# btn.net
KiCad netlist of a schematic drawn in Altium Designer
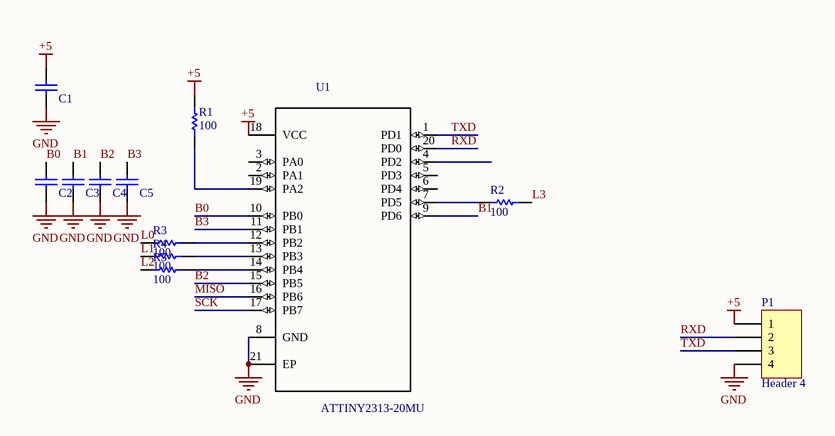
[diagram p0: btn.SchDoc]

(export (version "E")
  (design (tool "Eeschema 10.0.6"))
  (components
    (comp (ref "C1")
      (value "Cap")
      (footprint "0603x")
      (description "Capacitor")
      (fields (field (name "PUBLISHER") "Altium Limited"))
      (libsource (lib "Miscellaneous Devices") (part "Cap"))
    )
    (comp (ref "C2")
      (value "Cap")
      (footprint "0603x")
      (description "Capacitor")
      (fields (field (name "PUBLISHER") "Altium Limited"))
      (libsource (lib "Miscellaneous Devices") (part "Cap"))
    )
    (comp (ref "C3")
      (value "Cap")
      (footprint "0603x")
      (description "Capacitor")
      (fields (field (name "PUBLISHER") "Altium Limited"))
      (libsource (lib "Miscellaneous Devices") (part "Cap"))
    )
    (comp (ref "C4")
      (value "Cap")
      (footprint "0603x")
      (description "Capacitor")
      (fields (field (name "PUBLISHER") "Altium Limited"))
      (libsource (lib "Miscellaneous Devices") (part "Cap"))
    )
    (comp (ref "C5")
      (value "Cap")
      (footprint "0603x")
      (description "Capacitor")
      (fields (field (name "PUBLISHER") "Altium Limited"))
      (libsource (lib "Miscellaneous Devices") (part "Cap"))
    )
    (comp (ref "P1")
      (value "Header 4")
      (footprint "HDR1X4")
      (description "Header, 4-Pin")
      (fields (field (name "PUBLISHER") "Altium Limited"))
      (libsource (lib "Miscellaneous Connectors") (part "Header 4"))
    )
    (comp (ref "R1")
      (value "100")
      (footprint "0402x")
      (description "Resistor")
      (fields (field (name "PUBLISHER") "Altium Limited"))
      (libsource (lib "Miscellaneous Devices") (part "Res1"))
    )
    (comp (ref "R2")
      (value "100")
      (footprint "0603x")
      (description "Resistor")
      (fields (field (name "PUBLISHER") "Altium Limited"))
      (libsource (lib "Miscellaneous Devices") (part "Res1"))
    )
    (comp (ref "R3")
      (value "100")
      (footprint "0603x")
      (description "Resistor")
      (fields (field (name "PUBLISHER") "Altium Limited"))
      (libsource (lib "Miscellaneous Devices") (part "Res1"))
    )
    (comp (ref "R4")
      (value "100")
      (footprint "0603x")
      (description "Resistor")
      (fields (field (name "PUBLISHER") "Altium Limited"))
      (libsource (lib "Miscellaneous Devices") (part "Res1"))
    )
    (comp (ref "R5")
      (value "100")
      (footprint "0603x")
      (description "Resistor")
      (fields (field (name "PUBLISHER") "Altium Limited"))
      (libsource (lib "Miscellaneous Devices") (part "Res1"))
    )
    (comp (ref "U1")
      (value "ATTINY2313-20MU")
      (footprint "*QFN50P400X400X80-21N")
      (description "ATtiny Series 20 MHz 2 KB Flash 128 B SRAM 8-Bit Microcontroller - QFN-20")
      (fields (field (name "MF") "Microchip"))
      (libsource (lib "EDDLib") (part "ATTINY2313-20MU"))
    )
  )
  (nets
    (net (code "1") (name "+5") (class "Default")
      (node (ref "C1") (pin "1") (pinfunction "1_1") (pintype "passive"))
      (node (ref "P1") (pin "1") (pinfunction "1_1") (pintype "passive"))
      (node (ref "R1") (pin "1") (pinfunction "1_1") (pintype "passive"))
      (node (ref "U1") (pin "18") (pinfunction "VCC_18") (pintype "power_in"))
    )
    (net (code "2") (name "/B0") (class "Default")
      (node (ref "C2") (pin "1") (pinfunction "1_1") (pintype "passive"))
      (node (ref "U1") (pin "10") (pinfunction "PB0_10") (pintype "bidirectional"))
    )
    (net (code "3") (name "/B1") (class "Default")
      (node (ref "C3") (pin "1") (pinfunction "1_1") (pintype "passive"))
      (node (ref "U1") (pin "9") (pinfunction "PD6_9") (pintype "bidirectional"))
    )
    (net (code "4") (name "/B2") (class "Default")
      (node (ref "C4") (pin "1") (pinfunction "1_1") (pintype "passive"))
      (node (ref "U1") (pin "15") (pinfunction "PB5_15") (pintype "bidirectional"))
    )
    (net (code "5") (name "/B3") (class "Default")
      (node (ref "C5") (pin "1") (pinfunction "1_1") (pintype "passive"))
      (node (ref "U1") (pin "11") (pinfunction "PB1_11") (pintype "bidirectional"))
    )
    (net (code "6") (name "/L0") (class "Default")
      (node (ref "R3") (pin "1") (pinfunction "1_1") (pintype "passive"))
    )
    (net (code "7") (name "/L1") (class "Default")
      (node (ref "R4") (pin "1") (pinfunction "1_1") (pintype "passive"))
    )
    (net (code "8") (name "/L2") (class "Default")
      (node (ref "R5") (pin "1") (pinfunction "1_1") (pintype "passive"))
    )
    (net (code "9") (name "/L3") (class "Default")
      (node (ref "R2") (pin "2") (pinfunction "2_2") (pintype "passive"))
    )
    (net (code "10") (name "/MISO") (class "Default")
      (node (ref "U1") (pin "16") (pinfunction "PB6_16") (pintype "bidirectional"))
    )
    (net (code "11") (name "/RXD") (class "Default")
      (node (ref "P1") (pin "2") (pinfunction "2_2") (pintype "passive"))
      (node (ref "U1") (pin "20") (pinfunction "PD0_20") (pintype "bidirectional"))
    )
    (net (code "12") (name "/SCK") (class "Default")
      (node (ref "U1") (pin "17") (pinfunction "PB7_17") (pintype "bidirectional"))
    )
    (net (code "13") (name "/TXD") (class "Default")
      (node (ref "P1") (pin "3") (pinfunction "3_3") (pintype "passive"))
      (node (ref "U1") (pin "1") (pinfunction "PD1_1") (pintype "bidirectional"))
    )
    (net (code "14") (name "GND") (class "Default")
      (node (ref "C1") (pin "2") (pinfunction "2_2") (pintype "passive"))
      (node (ref "C2") (pin "2") (pinfunction "2_2") (pintype "passive"))
      (node (ref "C3") (pin "2") (pinfunction "2_2") (pintype "passive"))
      (node (ref "C4") (pin "2") (pinfunction "2_2") (pintype "passive"))
      (node (ref "C5") (pin "2") (pinfunction "2_2") (pintype "passive"))
      (node (ref "P1") (pin "4") (pinfunction "4_4") (pintype "passive"))
      (node (ref "U1") (pin "21") (pinfunction "EP_21") (pintype "passive"))
      (node (ref "U1") (pin "8") (pinfunction "GND_8") (pintype "passive"))
    )
    (net (code "15") (name "Net-(U1-PA2)") (class "Default")
      (node (ref "R1") (pin "2") (pinfunction "2_2") (pintype "passive"))
      (node (ref "U1") (pin "19") (pinfunction "PA2_19") (pintype "bidirectional"))
    )
    (net (code "16") (name "Net-(U1-PB2)") (class "Default")
      (node (ref "R3") (pin "2") (pinfunction "2_2") (pintype "passive"))
      (node (ref "U1") (pin "12") (pinfunction "PB2_12") (pintype "bidirectional"))
    )
    (net (code "17") (name "Net-(U1-PB3)") (class "Default")
      (node (ref "R4") (pin "2") (pinfunction "2_2") (pintype "passive"))
      (node (ref "U1") (pin "13") (pinfunction "PB3_13") (pintype "bidirectional"))
    )
    (net (code "18") (name "Net-(U1-PB4)") (class "Default")
      (node (ref "R5") (pin "2") (pinfunction "2_2") (pintype "passive"))
      (node (ref "U1") (pin "14") (pinfunction "PB4_14") (pintype "bidirectional"))
    )
    (net (code "19") (name "Net-(U1-PD5)") (class "Default")
      (node (ref "R2") (pin "1") (pinfunction "1_1") (pintype "passive"))
      (node (ref "U1") (pin "7") (pinfunction "PD5_7") (pintype "bidirectional"))
    )
    (net (code "20") (name "unconnected-(U1-PA0-Pad3)") (class "Default")
      (node (ref "U1") (pin "3") (pinfunction "PA0_3") (pintype "bidirectional"))
    )
    (net (code "21") (name "unconnected-(U1-PA1-Pad2)") (class "Default")
      (node (ref "U1") (pin "2") (pinfunction "PA1_2") (pintype "bidirectional"))
    )
    (net (code "22") (name "unconnected-(U1-PD2-Pad4)") (class "Default")
      (node (ref "U1") (pin "4") (pinfunction "PD2_4") (pintype "bidirectional"))
    )
    (net (code "23") (name "unconnected-(U1-PD3-Pad5)") (class "Default")
      (node (ref "U1") (pin "5") (pinfunction "PD3_5") (pintype "bidirectional"))
    )
    (net (code "24") (name "unconnected-(U1-PD4-Pad6)") (class "Default")
      (node (ref "U1") (pin "6") (pinfunction "PD4_6") (pintype "bidirectional"))
    )
  )
)
